# Button_V1_1.net
KiCad netlist of a schematic drawn in EAGLE
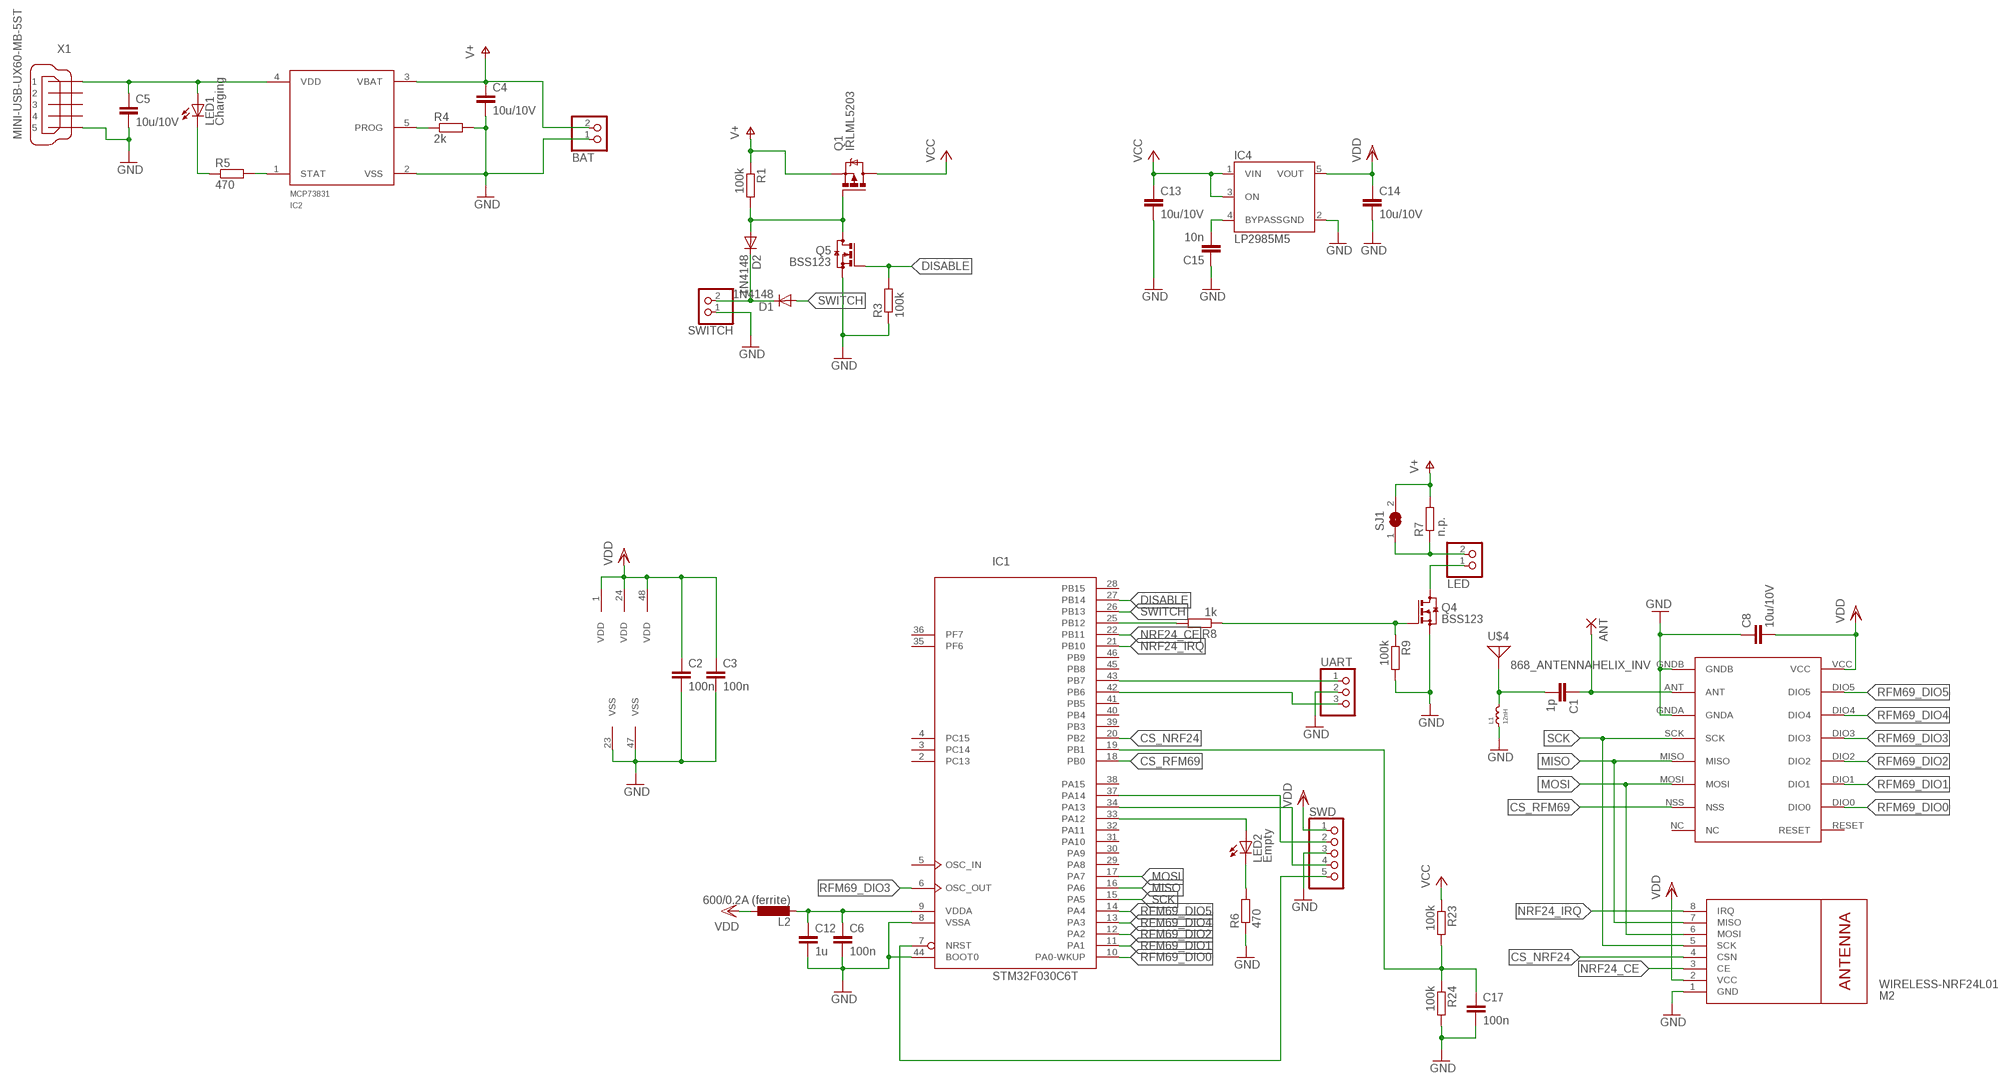
[diagram p0: schematic, sheet 1]

(export (version "E")
  (design (tool "Eeschema 10.0.6"))
  (components
    (comp (ref "ANT")
      (value "1,6/0,8")
      (footprint "eagle-import:1,6_0,8")
      (libsource (lib "eagle-import") (part "1,6/0,8"))
    )
    (comp (ref "BAT")
      (value "PINHD-1X2")
      (footprint "eagle-import:1X02")
      (libsource (lib "eagle-import") (part "PINHD-1X2"))
    )
    (comp (ref "C1")
      (value "1p")
      (footprint "eagle-import:C0603")
      (libsource (lib "eagle-import") (part "C-EUC0603"))
    )
    (comp (ref "C2")
      (value "100n")
      (footprint "eagle-import:C0603")
      (libsource (lib "eagle-import") (part "C-EUC0603"))
    )
    (comp (ref "C3")
      (value "100n")
      (footprint "eagle-import:C0603")
      (libsource (lib "eagle-import") (part "C-EUC0603"))
    )
    (comp (ref "C4")
      (value "10u/10V")
      (footprint "eagle-import:C1206")
      (libsource (lib "eagle-import") (part "C-EUC1206"))
    )
    (comp (ref "C5")
      (value "10u/10V")
      (footprint "eagle-import:C1206")
      (libsource (lib "eagle-import") (part "C-EUC1206"))
    )
    (comp (ref "C6")
      (value "100n")
      (footprint "eagle-import:C0603")
      (libsource (lib "eagle-import") (part "C-EUC0603"))
    )
    (comp (ref "C8")
      (value "10u/10V")
      (footprint "eagle-import:C1206")
      (libsource (lib "eagle-import") (part "C-EUC1206"))
    )
    (comp (ref "C12")
      (value "1u")
      (footprint "eagle-import:C0603")
      (libsource (lib "eagle-import") (part "C-EUC0603"))
    )
    (comp (ref "C13")
      (value "10u/10V")
      (footprint "eagle-import:C1206")
      (libsource (lib "eagle-import") (part "C-EUC1206"))
    )
    (comp (ref "C14")
      (value "10u/10V")
      (footprint "eagle-import:C1206")
      (libsource (lib "eagle-import") (part "C-EUC1206"))
    )
    (comp (ref "C15")
      (value "10n")
      (footprint "eagle-import:C0603")
      (libsource (lib "eagle-import") (part "C-EUC0603"))
    )
    (comp (ref "C17")
      (value "100n")
      (footprint "eagle-import:C0603")
      (libsource (lib "eagle-import") (part "C-EUC0603"))
    )
    (comp (ref "D1")
      (value "1N4148")
      (footprint "eagle-import:SOD323-W")
      (libsource (lib "eagle-import") (part "DIODE-SOD323-W"))
    )
    (comp (ref "D2")
      (value "1N4148")
      (footprint "eagle-import:SOD323-W")
      (libsource (lib "eagle-import") (part "DIODE-SOD323-W"))
    )
    (comp (ref "IC1")
      (value "STM32F030C6T")
      (footprint "eagle-import:LQFP48")
      (libsource (lib "eagle-import") (part "STM32F030CT6"))
    )
    (comp (ref "IC2")
      (value "MCP73831")
      (footprint "eagle-import:SOT23-5")
      (libsource (lib "eagle-import") (part "MCP73831"))
    )
    (comp (ref "IC4")
      (value "LP2985M5")
      (footprint "eagle-import:SOT23-5")
      (libsource (lib "eagle-import") (part "LP2985M5"))
    )
    (comp (ref "L1")
      (value "12nH")
      (footprint "eagle-import:0603")
      (libsource (lib "eagle-import") (part "RF-INDUCTOR.0603"))
    )
    (comp (ref "L2")
      (value "600/0.2A (ferrite)")
      (footprint "eagle-import:L2012C")
      (libsource (lib "eagle-import") (part "L-EUL2012C"))
    )
    (comp (ref "LED")
      (value "PINHD-1X2")
      (footprint "eagle-import:1X02")
      (libsource (lib "eagle-import") (part "PINHD-1X2"))
    )
    (comp (ref "LED1")
      (value "Charging")
      (footprint "eagle-import:CHIPLED_0603")
      (libsource (lib "eagle-import") (part "LEDCHIPLED_0603"))
    )
    (comp (ref "LED2")
      (value "Empty")
      (footprint "eagle-import:CHIPLED_0603")
      (libsource (lib "eagle-import") (part "LEDCHIPLED_0603"))
    )
    (comp (ref "M2")
      (value "WIRELESS-NRF24L01")
      (footprint "eagle-import:WIRELESS-NRF24L01")
      (libsource (lib "eagle-import") (part "WIRELESS-NRF24L01"))
    )
    (comp (ref "Q1")
      (value "IRLML5203")
      (footprint "eagle-import:MICRO3")
      (libsource (lib "eagle-import") (part "IRLML5203"))
    )
    (comp (ref "Q4")
      (value "BSS123")
      (footprint "eagle-import:SOT23")
      (libsource (lib "eagle-import") (part "BSS123"))
    )
    (comp (ref "Q5")
      (value "BSS123")
      (footprint "eagle-import:SOT23")
      (libsource (lib "eagle-import") (part "BSS123"))
    )
    (comp (ref "R1")
      (value "100k")
      (footprint "eagle-import:R0603")
      (libsource (lib "eagle-import") (part "R-EU_R0603"))
    )
    (comp (ref "R3")
      (value "100k")
      (footprint "eagle-import:R0603")
      (libsource (lib "eagle-import") (part "R-EU_R0603"))
    )
    (comp (ref "R4")
      (value "2k")
      (footprint "eagle-import:R0603")
      (libsource (lib "eagle-import") (part "R-EU_R0603"))
    )
    (comp (ref "R5")
      (value "470")
      (footprint "eagle-import:R0603")
      (libsource (lib "eagle-import") (part "R-EU_R0603"))
    )
    (comp (ref "R6")
      (value "470")
      (footprint "eagle-import:R0603")
      (libsource (lib "eagle-import") (part "R-EU_R0603"))
    )
    (comp (ref "R7")
      (value "n.p.")
      (footprint "eagle-import:R1206")
      (libsource (lib "eagle-import") (part "R-EU_R1206"))
    )
    (comp (ref "R8")
      (value "1k")
      (footprint "eagle-import:R0603")
      (libsource (lib "eagle-import") (part "R-EU_R0603"))
    )
    (comp (ref "R9")
      (value "100k")
      (footprint "eagle-import:R0603")
      (libsource (lib "eagle-import") (part "R-EU_R0603"))
    )
    (comp (ref "R23")
      (value "100k")
      (footprint "eagle-import:R0603")
      (libsource (lib "eagle-import") (part "R-EU_R0603"))
    )
    (comp (ref "R24")
      (value "100k")
      (footprint "eagle-import:R0603")
      (libsource (lib "eagle-import") (part "R-EU_R0603"))
    )
    (comp (ref "SJ1") (value "SJ") (footprint "eagle-import:SJ") (libsource (lib "eagle-import") (part "SJ")))
    (comp (ref "SWD")
      (value "PINHD-1X5")
      (footprint "eagle-import:1X05")
      (libsource (lib "eagle-import") (part "PINHD-1X5"))
    )
    (comp (ref "SWITCH")
      (value "PINHD-1X2")
      (footprint "eagle-import:1X02")
      (libsource (lib "eagle-import") (part "PINHD-1X2"))
    )
    (comp (ref "U$1")
      (value "RFM69HW")
      (footprint "eagle-import:RFM")
      (libsource (lib "eagle-import") (part "RFM69HW"))
    )
    (comp (ref "U$4")
      (value "868_ANTENNAHELIX_INV")
      (footprint "eagle-import:HELIX_868_INV")
      (libsource (lib "eagle-import") (part "868_ANTENNAHELIX_INV"))
    )
    (comp (ref "UART")
      (value "PINHD-1X3")
      (footprint "eagle-import:1X03")
      (libsource (lib "eagle-import") (part "PINHD-1X3"))
    )
    (comp (ref "X1")
      (value "MINI-USB-UX60-MB-5ST")
      (footprint "eagle-import:UX60-MB-5ST")
      (libsource (lib "eagle-import") (part "MINI-USB-UX60-MB-5ST"))
    )
  )
  (nets
    (net (code "1") (name "CS_NRF24") (class "Default")
      (node (ref "IC1") (pin "20") (pinfunction "PB2_20") (pintype "bidirectional"))
      (node (ref "M2") (pin "4") (pinfunction "CSN_4") (pintype "bidirectional"))
    )
    (net (code "2") (name "CS_RFM69") (class "Default")
      (node (ref "IC1") (pin "18") (pinfunction "PB0_18") (pintype "bidirectional"))
      (node (ref "U$1") (pin "NSS") (pinfunction "NSS_NSS") (pintype "bidirectional"))
    )
    (net (code "3") (name "DISABLE") (class "Default")
      (node (ref "IC1") (pin "27") (pinfunction "PB14_27") (pintype "bidirectional"))
      (node (ref "Q5") (pin "1") (pinfunction "G_1") (pintype "passive"))
      (node (ref "R3") (pin "2") (pinfunction "2_2") (pintype "passive"))
    )
    (net (code "4") (name "GND") (class "Default")
      (node (ref "BAT") (pin "1") (pinfunction "1_1") (pintype "passive"))
      (node (ref "C12") (pin "2") (pinfunction "2_2") (pintype "passive"))
      (node (ref "C13") (pin "2") (pinfunction "2_2") (pintype "passive"))
      (node (ref "C14") (pin "2") (pinfunction "2_2") (pintype "passive"))
      (node (ref "C15") (pin "1") (pinfunction "1_1") (pintype "passive"))
      (node (ref "C17") (pin "2") (pinfunction "2_2") (pintype "passive"))
      (node (ref "C2") (pin "2") (pinfunction "2_2") (pintype "passive"))
      (node (ref "C3") (pin "2") (pinfunction "2_2") (pintype "passive"))
      (node (ref "C4") (pin "2") (pinfunction "2_2") (pintype "passive"))
      (node (ref "C5") (pin "2") (pinfunction "2_2") (pintype "passive"))
      (node (ref "C6") (pin "2") (pinfunction "2_2") (pintype "passive"))
      (node (ref "C8") (pin "1") (pinfunction "1_1") (pintype "passive"))
      (node (ref "IC1") (pin "23") (pinfunction "VSS_23") (pintype "power_in"))
      (node (ref "IC1") (pin "44") (pinfunction "BOOT0_44") (pintype "input"))
      (node (ref "IC1") (pin "47") (pinfunction "VSS_47") (pintype "power_in"))
      (node (ref "IC1") (pin "8") (pinfunction "VSSA_8") (pintype "power_in"))
      (node (ref "IC2") (pin "2") (pinfunction "VSS_2") (pintype "bidirectional"))
      (node (ref "IC4") (pin "2") (pinfunction "GND_2") (pintype "power_in"))
      (node (ref "L1") (pin "1") (pinfunction "1_1") (pintype "passive"))
      (node (ref "M2") (pin "1") (pinfunction "GND_1") (pintype "power_in"))
      (node (ref "Q4") (pin "2") (pinfunction "S_2") (pintype "passive"))
      (node (ref "Q5") (pin "2") (pinfunction "S_2") (pintype "passive"))
      (node (ref "R24") (pin "2") (pinfunction "2_2") (pintype "passive"))
      (node (ref "R3") (pin "1") (pinfunction "1_1") (pintype "passive"))
      (node (ref "R4") (pin "2") (pinfunction "2_2") (pintype "passive"))
      (node (ref "R6") (pin "1") (pinfunction "1_1") (pintype "passive"))
      (node (ref "R9") (pin "2") (pinfunction "2_2") (pintype "passive"))
      (node (ref "SWD") (pin "3") (pinfunction "3_3") (pintype "passive"))
      (node (ref "SWITCH") (pin "1") (pinfunction "1_1") (pintype "passive"))
      (node (ref "U$1") (pin "GNDA") (pinfunction "GNDA_GNDA") (pintype "bidirectional"))
      (node (ref "U$1") (pin "GNDB") (pinfunction "GNDB_GNDB") (pintype "bidirectional"))
      (node (ref "UART") (pin "2") (pinfunction "2_2") (pintype "passive"))
      (node (ref "X1") (pin "5") (pinfunction "5_5") (pintype "input"))
    )
    (net (code "5") (name "MISO") (class "Default")
      (node (ref "IC1") (pin "16") (pinfunction "PA6_16") (pintype "bidirectional"))
      (node (ref "M2") (pin "7") (pinfunction "MISO_7") (pintype "bidirectional"))
      (node (ref "U$1") (pin "MISO") (pinfunction "MISO_MISO") (pintype "bidirectional"))
    )
    (net (code "6") (name "MOSI") (class "Default")
      (node (ref "IC1") (pin "17") (pinfunction "PA7_17") (pintype "bidirectional"))
      (node (ref "M2") (pin "6") (pinfunction "MOSI_6") (pintype "bidirectional"))
      (node (ref "U$1") (pin "MOSI") (pinfunction "MOSI_MOSI") (pintype "bidirectional"))
    )
    (net (code "7") (name "NRF24_CE") (class "Default")
      (node (ref "IC1") (pin "22") (pinfunction "PB11_22") (pintype "bidirectional"))
      (node (ref "M2") (pin "3") (pinfunction "CE_3") (pintype "bidirectional"))
    )
    (net (code "8") (name "NRF24_IRQ") (class "Default")
      (node (ref "IC1") (pin "21") (pinfunction "PB10_21") (pintype "bidirectional"))
      (node (ref "M2") (pin "8") (pinfunction "IRQ_8") (pintype "bidirectional"))
    )
    (net (code "9") (name "Net-(ANT-P)") (class "Default")
      (node (ref "ANT") (pin "1") (pinfunction "P_1") (pintype "passive"))
      (node (ref "C1") (pin "1") (pinfunction "1_1") (pintype "passive"))
      (node (ref "U$1") (pin "ANT") (pinfunction "ANT_ANT") (pintype "bidirectional"))
    )
    (net (code "10") (name "Net-(C1-Pad2)") (class "Default")
      (node (ref "C1") (pin "2") (pinfunction "2_2") (pintype "passive"))
      (node (ref "L1") (pin "2") (pinfunction "2_2") (pintype "passive"))
      (node (ref "U$4") (pin "ANT") (pinfunction "1_ANT") (pintype "output"))
      (node (ref "U$4") (pin "P$10") (pinfunction "1_P$10") (pintype "output"))
      (node (ref "U$4") (pin "P$11") (pinfunction "1_P$11") (pintype "output"))
      (node (ref "U$4") (pin "P$12") (pinfunction "1_P$12") (pintype "output"))
      (node (ref "U$4") (pin "P$13") (pinfunction "1_P$13") (pintype "output"))
      (node (ref "U$4") (pin "P$14") (pinfunction "1_P$14") (pintype "output"))
      (node (ref "U$4") (pin "P$15") (pinfunction "1_P$15") (pintype "output"))
      (node (ref "U$4") (pin "P$16") (pinfunction "1_P$16") (pintype "output"))
      (node (ref "U$4") (pin "P$17") (pinfunction "1_P$17") (pintype "output"))
      (node (ref "U$4") (pin "P$18") (pinfunction "1_P$18") (pintype "output"))
      (node (ref "U$4") (pin "P$19") (pinfunction "1_P$19") (pintype "output"))
      (node (ref "U$4") (pin "P$2") (pinfunction "1_P$2") (pintype "output"))
      (node (ref "U$4") (pin "P$20") (pinfunction "1_P$20") (pintype "output"))
      (node (ref "U$4") (pin "P$3") (pinfunction "1_P$3") (pintype "output"))
      (node (ref "U$4") (pin "P$4") (pinfunction "1_P$4") (pintype "output"))
      (node (ref "U$4") (pin "P$5") (pinfunction "1_P$5") (pintype "output"))
      (node (ref "U$4") (pin "P$6") (pinfunction "1_P$6") (pintype "output"))
      (node (ref "U$4") (pin "P$7") (pinfunction "1_P$7") (pintype "output"))
      (node (ref "U$4") (pin "P$8") (pinfunction "1_P$8") (pintype "output"))
      (node (ref "U$4") (pin "P$9") (pinfunction "1_P$9") (pintype "output"))
    )
    (net (code "11") (name "Net-(D1-PadC)") (class "Default")
      (node (ref "D1") (pin "C") (pinfunction "C_C") (pintype "passive"))
      (node (ref "D2") (pin "C") (pinfunction "C_C") (pintype "passive"))
      (node (ref "SWITCH") (pin "2") (pinfunction "2_2") (pintype "passive"))
    )
    (net (code "12") (name "Net-(IC1A-NRST)") (class "Default")
      (node (ref "IC1") (pin "7") (pinfunction "NRST_7") (pintype "bidirectional"))
      (node (ref "SWD") (pin "5") (pinfunction "5_5") (pintype "passive"))
    )
    (net (code "13") (name "Net-(IC1A-PA12)") (class "Default")
      (node (ref "IC1") (pin "33") (pinfunction "PA12_33") (pintype "bidirectional"))
      (node (ref "LED2") (pin "A") (pinfunction "A_A") (pintype "passive"))
    )
    (net (code "14") (name "Net-(IC1A-PA13)") (class "Default")
      (node (ref "IC1") (pin "34") (pinfunction "PA13_34") (pintype "bidirectional"))
      (node (ref "SWD") (pin "4") (pinfunction "4_4") (pintype "passive"))
    )
    (net (code "15") (name "Net-(IC1A-PA14)") (class "Default")
      (node (ref "IC1") (pin "37") (pinfunction "PA14_37") (pintype "bidirectional"))
      (node (ref "SWD") (pin "2") (pinfunction "2_2") (pintype "passive"))
    )
    (net (code "16") (name "Net-(IC1A-PB1)") (class "Default")
      (node (ref "C17") (pin "1") (pinfunction "1_1") (pintype "passive"))
      (node (ref "IC1") (pin "19") (pinfunction "PB1_19") (pintype "bidirectional"))
      (node (ref "R23") (pin "2") (pinfunction "2_2") (pintype "passive"))
      (node (ref "R24") (pin "1") (pinfunction "1_1") (pintype "passive"))
    )
    (net (code "17") (name "Net-(IC1A-PB6)") (class "Default")
      (node (ref "IC1") (pin "42") (pinfunction "PB6_42") (pintype "bidirectional"))
      (node (ref "UART") (pin "3") (pinfunction "3_3") (pintype "passive"))
    )
    (net (code "18") (name "Net-(IC1A-PB7)") (class "Default")
      (node (ref "IC1") (pin "43") (pinfunction "PB7_43") (pintype "bidirectional"))
      (node (ref "UART") (pin "1") (pinfunction "1_1") (pintype "passive"))
    )
    (net (code "19") (name "Net-(IC1A-PB12)") (class "Default")
      (node (ref "IC1") (pin "25") (pinfunction "PB12_25") (pintype "bidirectional"))
      (node (ref "R8") (pin "2") (pinfunction "2_2") (pintype "passive"))
    )
    (net (code "20") (name "Net-(IC1A-VDDA)") (class "Default")
      (node (ref "C12") (pin "1") (pinfunction "1_1") (pintype "passive"))
      (node (ref "C6") (pin "1") (pinfunction "1_1") (pintype "passive"))
      (node (ref "IC1") (pin "9") (pinfunction "VDDA_9") (pintype "power_in"))
      (node (ref "L2") (pin "2") (pinfunction "2_2") (pintype "passive"))
    )
    (net (code "21") (name "Net-(IC2-PROG)") (class "Default")
      (node (ref "IC2") (pin "5") (pinfunction "PROG_5") (pintype "bidirectional"))
      (node (ref "R4") (pin "1") (pinfunction "1_1") (pintype "passive"))
    )
    (net (code "22") (name "Net-(IC2-STAT)") (class "Default")
      (node (ref "IC2") (pin "1") (pinfunction "STAT_1") (pintype "bidirectional"))
      (node (ref "R5") (pin "2") (pinfunction "2_2") (pintype "passive"))
    )
    (net (code "23") (name "Net-(IC2-VDD)") (class "Default")
      (node (ref "C5") (pin "1") (pinfunction "1_1") (pintype "passive"))
      (node (ref "IC2") (pin "4") (pinfunction "VDD_4") (pintype "bidirectional"))
      (node (ref "LED1") (pin "A") (pinfunction "A_A") (pintype "passive"))
      (node (ref "X1") (pin "1") (pinfunction "1_1") (pintype "input"))
    )
    (net (code "24") (name "Net-(IC4-BYPASS)") (class "Default")
      (node (ref "C15") (pin "2") (pinfunction "2_2") (pintype "passive"))
      (node (ref "IC4") (pin "4") (pinfunction "BYPASS_4") (pintype "passive"))
    )
    (net (code "25") (name "Net-(LED-Pad2)") (class "Default")
      (node (ref "LED") (pin "2") (pinfunction "2_2") (pintype "passive"))
      (node (ref "R7") (pin "1") (pinfunction "1_1") (pintype "passive"))
      (node (ref "SJ1") (pin "1") (pinfunction "1_1") (pintype "passive"))
    )
    (net (code "26") (name "Net-(LED1-PadC)") (class "Default")
      (node (ref "LED1") (pin "C") (pinfunction "C_C") (pintype "passive"))
      (node (ref "R5") (pin "1") (pinfunction "1_1") (pintype "passive"))
    )
    (net (code "27") (name "Net-(LED2-PadC)") (class "Default")
      (node (ref "LED2") (pin "C") (pinfunction "C_C") (pintype "passive"))
      (node (ref "R6") (pin "2") (pinfunction "2_2") (pintype "passive"))
    )
    (net (code "28") (name "Net-(Q1-G)") (class "Default")
      (node (ref "D2") (pin "A") (pinfunction "A_A") (pintype "passive"))
      (node (ref "Q1") (pin "1") (pinfunction "G_1") (pintype "passive"))
      (node (ref "Q5") (pin "3") (pinfunction "D_3") (pintype "passive"))
      (node (ref "R1") (pin "2") (pinfunction "2_2") (pintype "passive"))
    )
    (net (code "29") (name "Net-(Q4-D)") (class "Default")
      (node (ref "LED") (pin "1") (pinfunction "1_1") (pintype "passive"))
      (node (ref "Q4") (pin "3") (pinfunction "D_3") (pintype "passive"))
    )
    (net (code "30") (name "Net-(Q4-G)") (class "Default")
      (node (ref "Q4") (pin "1") (pinfunction "G_1") (pintype "passive"))
      (node (ref "R8") (pin "1") (pinfunction "1_1") (pintype "passive"))
      (node (ref "R9") (pin "1") (pinfunction "1_1") (pintype "passive"))
    )
    (net (code "31") (name "RFM69_DIO0") (class "Default")
      (node (ref "IC1") (pin "10") (pinfunction "PA0-WKUP_10") (pintype "bidirectional"))
      (node (ref "U$1") (pin "DIO0") (pinfunction "DIO0_DIO0") (pintype "bidirectional"))
    )
    (net (code "32") (name "RFM69_DIO1") (class "Default")
      (node (ref "IC1") (pin "11") (pinfunction "PA1_11") (pintype "bidirectional"))
      (node (ref "U$1") (pin "DIO1") (pinfunction "DIO1_DIO1") (pintype "bidirectional"))
    )
    (net (code "33") (name "RFM69_DIO2") (class "Default")
      (node (ref "IC1") (pin "12") (pinfunction "PA2_12") (pintype "bidirectional"))
      (node (ref "U$1") (pin "DIO2") (pinfunction "DIO2_DIO2") (pintype "bidirectional"))
    )
    (net (code "34") (name "RFM69_DIO3") (class "Default")
      (node (ref "IC1") (pin "6") (pinfunction "OSC_OUT_6") (pintype "bidirectional"))
      (node (ref "U$1") (pin "DIO3") (pinfunction "DIO3_DIO3") (pintype "bidirectional"))
    )
    (net (code "35") (name "RFM69_DIO4") (class "Default")
      (node (ref "IC1") (pin "13") (pinfunction "PA3_13") (pintype "bidirectional"))
      (node (ref "U$1") (pin "DIO4") (pinfunction "DIO4_DIO4") (pintype "bidirectional"))
    )
    (net (code "36") (name "RFM69_DIO5") (class "Default")
      (node (ref "IC1") (pin "14") (pinfunction "PA4_14") (pintype "bidirectional"))
      (node (ref "U$1") (pin "DIO5") (pinfunction "DIO5_DIO5") (pintype "bidirectional"))
    )
    (net (code "37") (name "SCK") (class "Default")
      (node (ref "IC1") (pin "15") (pinfunction "PA5_15") (pintype "bidirectional"))
      (node (ref "M2") (pin "5") (pinfunction "SCK_5") (pintype "bidirectional"))
      (node (ref "U$1") (pin "SCK") (pinfunction "SCK_SCK") (pintype "bidirectional"))
    )
    (net (code "38") (name "SWITCH") (class "Default")
      (node (ref "D1") (pin "A") (pinfunction "A_A") (pintype "passive"))
      (node (ref "IC1") (pin "26") (pinfunction "PB13_26") (pintype "bidirectional"))
    )
    (net (code "39") (name "V+") (class "Default")
      (node (ref "BAT") (pin "2") (pinfunction "2_2") (pintype "passive"))
      (node (ref "C4") (pin "1") (pinfunction "1_1") (pintype "passive"))
      (node (ref "IC2") (pin "3") (pinfunction "VBAT_3") (pintype "bidirectional"))
      (node (ref "Q1") (pin "2") (pinfunction "S_2") (pintype "passive"))
      (node (ref "R1") (pin "1") (pinfunction "1_1") (pintype "passive"))
      (node (ref "R7") (pin "2") (pinfunction "2_2") (pintype "passive"))
      (node (ref "SJ1") (pin "2") (pinfunction "2_2") (pintype "passive"))
    )
    (net (code "40") (name "VCC") (class "Default")
      (node (ref "C13") (pin "1") (pinfunction "1_1") (pintype "passive"))
      (node (ref "IC4") (pin "1") (pinfunction "VIN_1") (pintype "power_in"))
      (node (ref "IC4") (pin "3") (pinfunction "ON_3") (pintype "input"))
      (node (ref "Q1") (pin "3") (pinfunction "D_3") (pintype "passive"))
      (node (ref "R23") (pin "1") (pinfunction "1_1") (pintype "passive"))
    )
    (net (code "41") (name "VDD") (class "Default")
      (node (ref "C14") (pin "1") (pinfunction "1_1") (pintype "passive"))
      (node (ref "C2") (pin "1") (pinfunction "1_1") (pintype "passive"))
      (node (ref "C3") (pin "1") (pinfunction "1_1") (pintype "passive"))
      (node (ref "C8") (pin "2") (pinfunction "2_2") (pintype "passive"))
      (node (ref "IC1") (pin "1") (pinfunction "VDD_1") (pintype "power_in"))
      (node (ref "IC1") (pin "24") (pinfunction "VDD_24") (pintype "power_in"))
      (node (ref "IC1") (pin "48") (pinfunction "VDD_48") (pintype "power_in"))
      (node (ref "IC4") (pin "5") (pinfunction "VOUT_5") (pintype "output"))
      (node (ref "L2") (pin "1") (pinfunction "1_1") (pintype "passive"))
      (node (ref "M2") (pin "2") (pinfunction "VCC_2") (pintype "power_in"))
      (node (ref "SWD") (pin "1") (pinfunction "1_1") (pintype "passive"))
      (node (ref "U$1") (pin "VCC") (pinfunction "VCC_VCC") (pintype "bidirectional"))
    )
    (net (code "42") (name "unconnected-(IC1A-OSC_IN-Pad5)") (class "Default")
      (node (ref "IC1") (pin "5") (pinfunction "OSC_IN_5") (pintype "bidirectional"))
    )
    (net (code "43") (name "unconnected-(IC1A-PA8-Pad29)") (class "Default")
      (node (ref "IC1") (pin "29") (pinfunction "PA8_29") (pintype "bidirectional"))
    )
    (net (code "44") (name "unconnected-(IC1A-PA9-Pad30)") (class "Default")
      (node (ref "IC1") (pin "30") (pinfunction "PA9_30") (pintype "bidirectional"))
    )
    (net (code "45") (name "unconnected-(IC1A-PA10-Pad31)") (class "Default")
      (node (ref "IC1") (pin "31") (pinfunction "PA10_31") (pintype "bidirectional"))
    )
    (net (code "46") (name "unconnected-(IC1A-PA11-Pad32)") (class "Default")
      (node (ref "IC1") (pin "32") (pinfunction "PA11_32") (pintype "bidirectional"))
    )
    (net (code "47") (name "unconnected-(IC1A-PA15-Pad38)") (class "Default")
      (node (ref "IC1") (pin "38") (pinfunction "PA15_38") (pintype "bidirectional"))
    )
    (net (code "48") (name "unconnected-(IC1A-PB3-Pad39)") (class "Default")
      (node (ref "IC1") (pin "39") (pinfunction "PB3_39") (pintype "bidirectional"))
    )
    (net (code "49") (name "unconnected-(IC1A-PB4-Pad40)") (class "Default")
      (node (ref "IC1") (pin "40") (pinfunction "PB4_40") (pintype "bidirectional"))
    )
    (net (code "50") (name "unconnected-(IC1A-PB5-Pad41)") (class "Default")
      (node (ref "IC1") (pin "41") (pinfunction "PB5_41") (pintype "bidirectional"))
    )
    (net (code "51") (name "unconnected-(IC1A-PB8-Pad45)") (class "Default")
      (node (ref "IC1") (pin "45") (pinfunction "PB8_45") (pintype "bidirectional"))
    )
    (net (code "52") (name "unconnected-(IC1A-PB9-Pad46)") (class "Default")
      (node (ref "IC1") (pin "46") (pinfunction "PB9_46") (pintype "bidirectional"))
    )
    (net (code "53") (name "unconnected-(IC1A-PB15-Pad28)") (class "Default")
      (node (ref "IC1") (pin "28") (pinfunction "PB15_28") (pintype "bidirectional"))
    )
    (net (code "54") (name "unconnected-(IC1A-PC13-Pad2)") (class "Default")
      (node (ref "IC1") (pin "2") (pinfunction "PC13_2") (pintype "bidirectional"))
    )
    (net (code "55") (name "unconnected-(IC1A-PC14-Pad3)") (class "Default")
      (node (ref "IC1") (pin "3") (pinfunction "PC14_3") (pintype "bidirectional"))
    )
    (net (code "56") (name "unconnected-(IC1A-PC15-Pad4)") (class "Default")
      (node (ref "IC1") (pin "4") (pinfunction "PC15_4") (pintype "bidirectional"))
    )
    (net (code "57") (name "unconnected-(IC1A-PF6-Pad35)") (class "Default")
      (node (ref "IC1") (pin "35") (pinfunction "PF6_35") (pintype "bidirectional"))
    )
    (net (code "58") (name "unconnected-(IC1A-PF7-Pad36)") (class "Default")
      (node (ref "IC1") (pin "36") (pinfunction "PF7_36") (pintype "bidirectional"))
    )
    (net (code "59") (name "unconnected-(U$1-PadNC)") (class "Default")
      (node (ref "U$1") (pin "NC") (pinfunction "NC_NC") (pintype "bidirectional"))
    )
    (net (code "60") (name "unconnected-(U$1-PadRESET)") (class "Default")
      (node (ref "U$1") (pin "RESET") (pinfunction "RESET_RESET") (pintype "bidirectional"))
    )
    (net (code "61") (name "unconnected-(X1-Pad2)") (class "Default")
      (node (ref "X1") (pin "2") (pinfunction "2_2") (pintype "input"))
    )
    (net (code "62") (name "unconnected-(X1-Pad3)") (class "Default")
      (node (ref "X1") (pin "3") (pinfunction "3_3") (pintype "input"))
    )
    (net (code "63") (name "unconnected-(X1-Pad4)") (class "Default")
      (node (ref "X1") (pin "4") (pinfunction "4_4") (pintype "input"))
    )
  )
)
